# Blinky.net
KiCad netlist of a schematic drawn in EAGLE
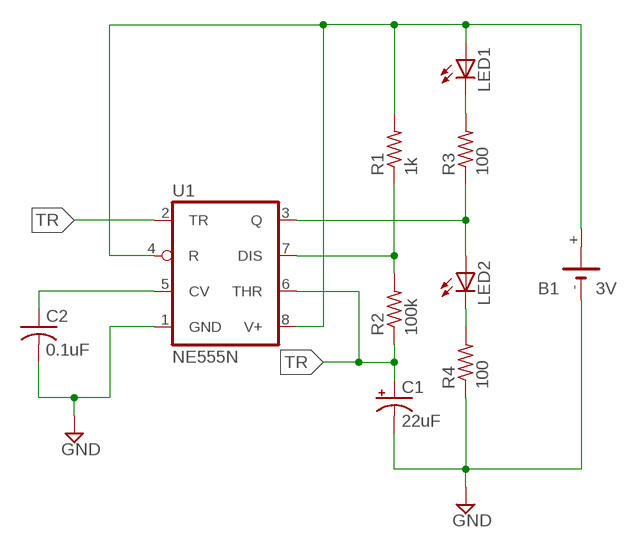
[diagram p0: schematic, sheet 1]

(export (version "E")
  (design (tool "Eeschema 10.0.6"))
  (components
    (comp (ref "B1")
      (value "3V")
      (footprint "eagle-import:CR2032H")
      (fields (field (name "SPICEPREFIX") "J"))
      (libsource (lib "eagle-import") (part "CR2032H"))
    )
    (comp (ref "C1")
      (value "22uF")
      (footprint "eagle-import:E1,8-4")
      (libsource (lib "eagle-import") (part "CPOL-USE1.8-4"))
    )
    (comp (ref "C2")
      (value "0.1uF")
      (footprint "eagle-import:C025-025X050")
      (libsource (lib "eagle-import") (part "C-US025-025X050"))
    )
    (comp (ref "LED1")
      (value "LED5MM")
      (footprint "eagle-import:LED5MM")
      (libsource (lib "eagle-import") (part "LED5MM"))
    )
    (comp (ref "LED2")
      (value "LED5MM")
      (footprint "eagle-import:LED5MM")
      (libsource (lib "eagle-import") (part "LED5MM"))
    )
    (comp (ref "R1")
      (value "1k")
      (footprint "eagle-import:0309_12")
      (libsource (lib "eagle-import") (part "R-US_0309/12"))
    )
    (comp (ref "R2")
      (value "100k")
      (footprint "eagle-import:0309_12")
      (libsource (lib "eagle-import") (part "R-US_0309/12"))
    )
    (comp (ref "R3")
      (value "100")
      (footprint "eagle-import:0309_12")
      (libsource (lib "eagle-import") (part "R-US_0309/12"))
    )
    (comp (ref "R4")
      (value "100")
      (footprint "eagle-import:0309_12")
      (libsource (lib "eagle-import") (part "R-US_0309/12"))
    )
    (comp (ref "U1")
      (value "NE555N")
      (footprint "eagle-import:DIL08")
      (fields (field (name "SPICEPREFIX") "X"))
      (libsource (lib "eagle-import") (part "555NNE"))
    )
  )
  (nets
    (net (code "1") (name "GND") (class "Default")
      (node (ref "B1") (pin "-") (pinfunction "-_-") (pintype "passive"))
      (node (ref "C1") (pin "-") (pinfunction "-_-") (pintype "passive"))
      (node (ref "C2") (pin "2") (pinfunction "2_2") (pintype "passive"))
      (node (ref "R4") (pin "1") (pinfunction "1_1") (pintype "passive"))
      (node (ref "U1") (pin "1") (pinfunction "GND_1") (pintype "power_in"))
    )
    (net (code "2") (name "Net-(LED1-C)") (class "Default")
      (node (ref "LED1") (pin "K") (pinfunction "C_K") (pintype "passive"))
      (node (ref "R3") (pin "2") (pinfunction "2_2") (pintype "passive"))
    )
    (net (code "3") (name "Net-(LED2-C)") (class "Default")
      (node (ref "LED2") (pin "K") (pinfunction "C_K") (pintype "passive"))
      (node (ref "R4") (pin "2") (pinfunction "2_2") (pintype "passive"))
    )
    (net (code "4") (name "Net-(U1-CV)") (class "Default")
      (node (ref "C2") (pin "1") (pinfunction "1_1") (pintype "passive"))
      (node (ref "U1") (pin "5") (pinfunction "CV_5") (pintype "input"))
    )
    (net (code "5") (name "Net-(U1-DIS)") (class "Default")
      (node (ref "R1") (pin "1") (pinfunction "1_1") (pintype "passive"))
      (node (ref "R2") (pin "2") (pinfunction "2_2") (pintype "passive"))
      (node (ref "U1") (pin "7") (pinfunction "DIS_7") (pintype "input"))
    )
    (net (code "6") (name "Net-(U1-Q)") (class "Default")
      (node (ref "LED2") (pin "A") (pinfunction "A_A") (pintype "passive"))
      (node (ref "R3") (pin "1") (pinfunction "1_1") (pintype "passive"))
      (node (ref "U1") (pin "3") (pinfunction "Q_3") (pintype "output"))
    )
    (net (code "7") (name "Net-(U1-R)") (class "Default")
      (node (ref "B1") (pin "+") (pinfunction "+_+") (pintype "passive"))
      (node (ref "LED1") (pin "A") (pinfunction "A_A") (pintype "passive"))
      (node (ref "R1") (pin "2") (pinfunction "2_2") (pintype "passive"))
      (node (ref "U1") (pin "4") (pinfunction "R_4") (pintype "input"))
      (node (ref "U1") (pin "8") (pinfunction "V+_8") (pintype "power_in"))
    )
    (net (code "8") (name "TR") (class "Default")
      (node (ref "C1") (pin "+") (pinfunction "+_+") (pintype "passive"))
      (node (ref "R2") (pin "1") (pinfunction "1_1") (pintype "passive"))
      (node (ref "U1") (pin "2") (pinfunction "TR_2") (pintype "input"))
      (node (ref "U1") (pin "6") (pinfunction "THR_6") (pintype "input"))
    )
    (net (code "9") (name "unconnected-(B1-+-Pad+@1)") (class "Default")
      (node (ref "B1") (pin "+@1") (pinfunction "+_+@1") (pintype "passive"))
    )
  )
)
